# sparkfun-nrf52832-breakout.net
KiCad netlist of a schematic drawn in EAGLE
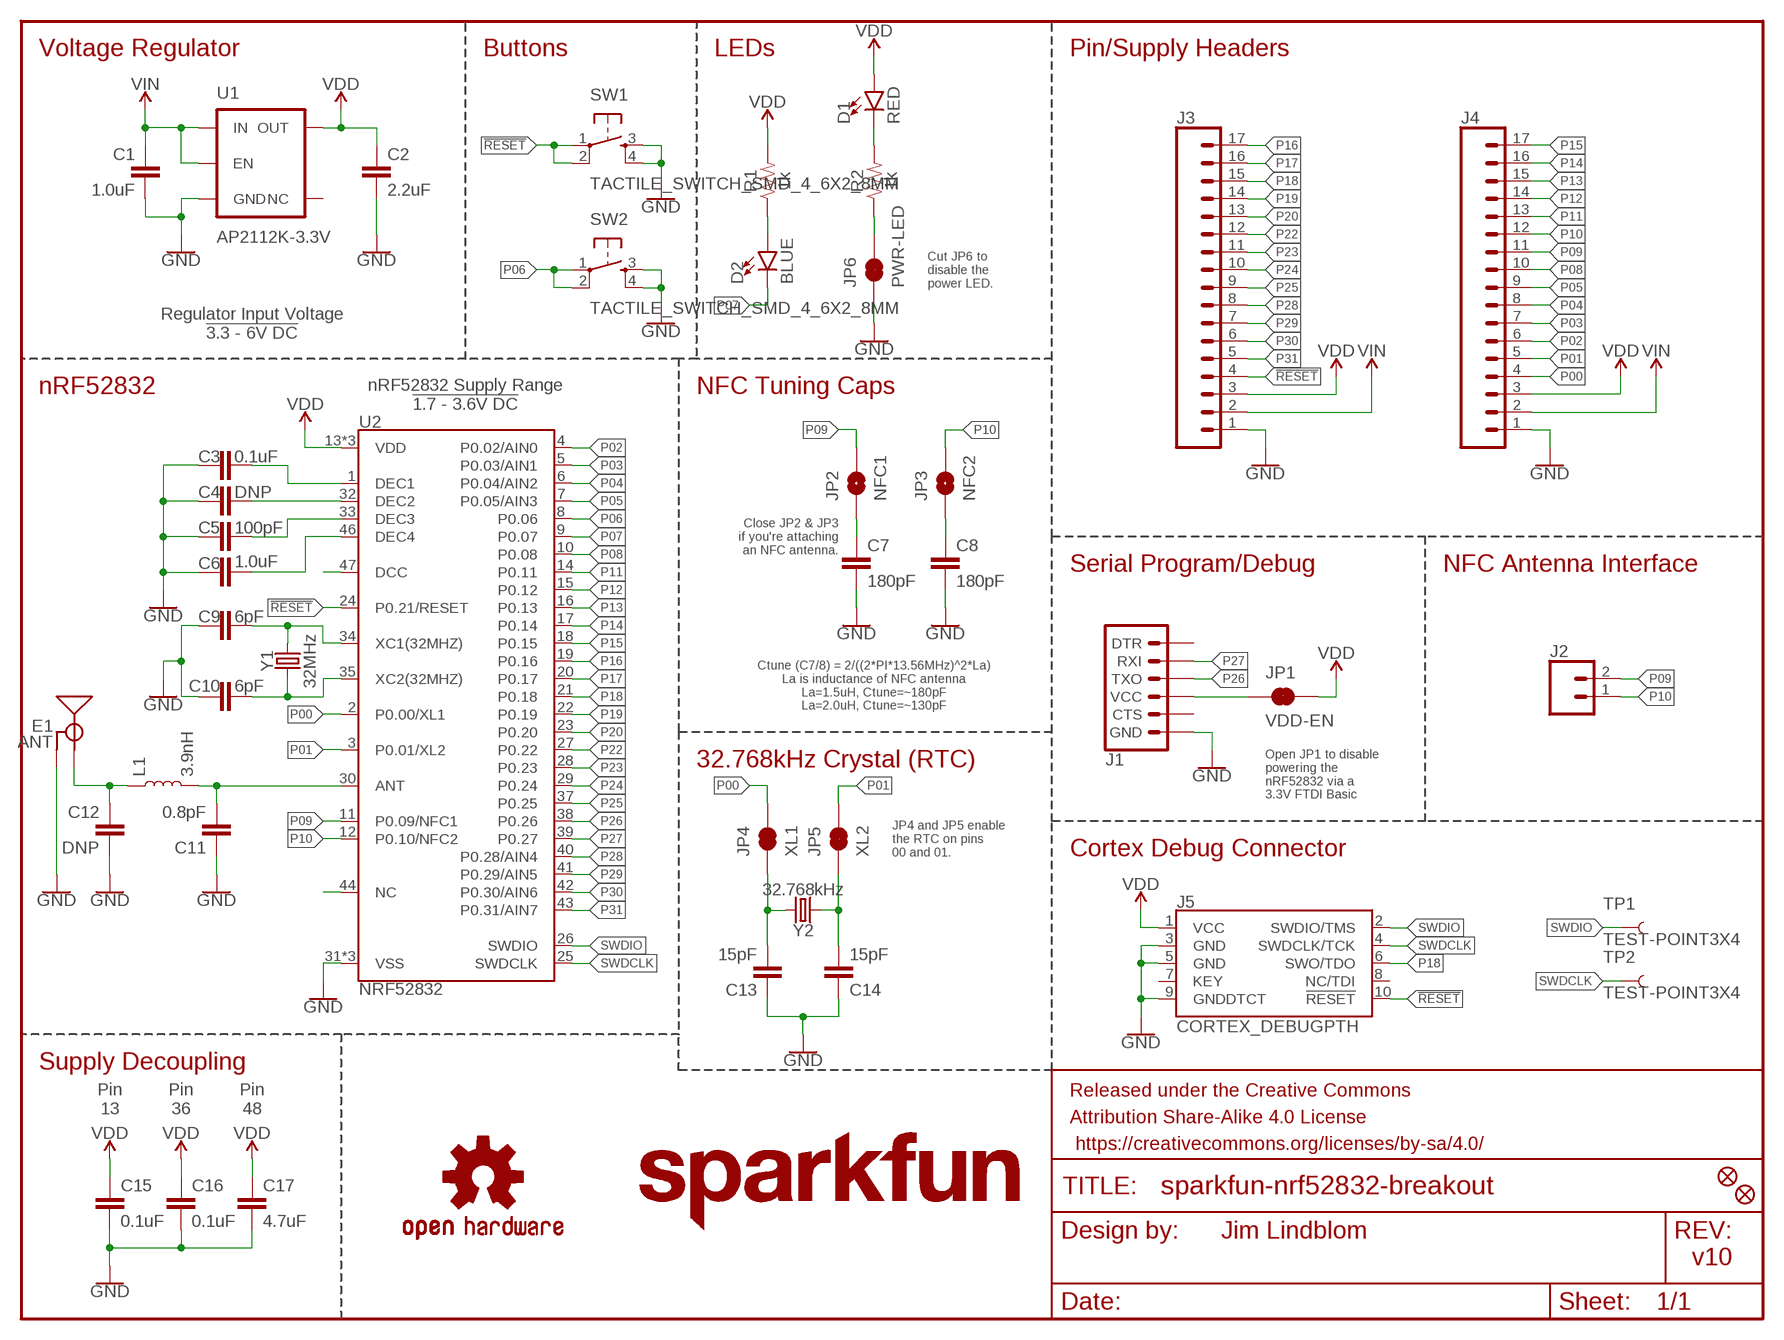
[diagram p0: schematic, sheet 1]

(export (version "E")
  (design (tool "Eeschema 10.0.6"))
  (components
    (comp (ref "C1")
      (value "1.0uF")
      (footprint "eagle-import:0603")
      (libsource (lib "eagle-import") (part "1.0UF-0603-16V-10%"))
    )
    (comp (ref "C2")
      (value "2.2uF")
      (footprint "eagle-import:0603")
      (libsource (lib "eagle-import") (part "2.2UF-0603-10V-20%"))
    )
    (comp (ref "C3")
      (value "0.1uF")
      (footprint "eagle-import:0402")
      (libsource (lib "eagle-import") (part "0.1UF-0402-16V-10%"))
    )
    (comp (ref "C4")
      (value "DNP")
      (footprint "eagle-import:0402")
      (libsource (lib "eagle-import") (part "CAP0402"))
    )
    (comp (ref "C5")
      (value "100pF")
      (footprint "eagle-import:0402")
      (libsource (lib "eagle-import") (part "100PF-0402-50V-5%"))
    )
    (comp (ref "C6")
      (value "1.0uF")
      (footprint "eagle-import:0402")
      (libsource (lib "eagle-import") (part "1.0UF-0402-16V-10%"))
    )
    (comp (ref "C7")
      (value "180pF")
      (footprint "eagle-import:0603")
      (libsource (lib "eagle-import") (part "180PF-0603-50V-5%"))
    )
    (comp (ref "C8")
      (value "180pF")
      (footprint "eagle-import:0603")
      (libsource (lib "eagle-import") (part "180PF-0603-50V-5%"))
    )
    (comp (ref "C9")
      (value "6pF")
      (footprint "eagle-import:0402")
      (libsource (lib "eagle-import") (part "6PF-0402-50V-0.5%"))
    )
    (comp (ref "C10")
      (value "6pF")
      (footprint "eagle-import:0402")
      (libsource (lib "eagle-import") (part "6PF-0402-50V-0.5%"))
    )
    (comp (ref "C11")
      (value "0.8pF")
      (footprint "eagle-import:0402")
      (libsource (lib "eagle-import") (part "0.8PF-0402-50V-0.1PF"))
    )
    (comp (ref "C12")
      (value "DNP")
      (footprint "eagle-import:0402")
      (libsource (lib "eagle-import") (part "CAP0402"))
    )
    (comp (ref "C13")
      (value "15pF")
      (footprint "eagle-import:0402")
      (libsource (lib "eagle-import") (part "15PF-0402-50V-5%"))
    )
    (comp (ref "C14")
      (value "15pF")
      (footprint "eagle-import:0402")
      (libsource (lib "eagle-import") (part "15PF-0402-50V-5%"))
    )
    (comp (ref "C15")
      (value "0.1uF")
      (footprint "eagle-import:0402")
      (libsource (lib "eagle-import") (part "0.1UF-0402-16V-10%"))
    )
    (comp (ref "C16")
      (value "0.1uF")
      (footprint "eagle-import:0402")
      (libsource (lib "eagle-import") (part "0.1UF-0402-16V-10%"))
    )
    (comp (ref "C17")
      (value "4.7uF")
      (footprint "eagle-import:0603")
      (libsource (lib "eagle-import") (part "4.7UF0603"))
    )
    (comp (ref "D1")
      (value "RED")
      (footprint "eagle-import:LED-0603")
      (libsource (lib "eagle-import") (part "LED-RED0603"))
    )
    (comp (ref "D2")
      (value "BLUE")
      (footprint "eagle-import:LED-0603")
      (libsource (lib "eagle-import") (part "LED-BLUE0603"))
    )
    (comp (ref "E1")
      (value "ANT")
      (footprint "eagle-import:TRACE_ANTENNA_2.4GHZ_15.2MM")
      (libsource (lib "eagle-import") (part "ANTENNA-GROUNDEDTRACE-15.2MM"))
    )
    (comp (ref "FD1")
      (value "FIDUCIALUFIDUCIAL")
      (footprint "eagle-import:FIDUCIAL-MICRO")
      (libsource (lib "eagle-import") (part "FIDUCIALUFIDUCIAL"))
    )
    (comp (ref "FD2")
      (value "FIDUCIALUFIDUCIAL")
      (footprint "eagle-import:FIDUCIAL-MICRO")
      (libsource (lib "eagle-import") (part "FIDUCIALUFIDUCIAL"))
    )
    (comp (ref "FRAME1")
      (value "FRAME-LETTER")
      (footprint "eagle-import:CREATIVE_COMMONS")
      (libsource (lib "eagle-import") (part "FRAME-LETTER"))
    )
    (comp (ref "J1")
      (value "ARDUINO_SERIAL_PROGRAMPTH")
      (footprint "eagle-import:1X06")
      (libsource (lib "eagle-import") (part "ARDUINO_SERIAL_PROGRAMPTH"))
    )
    (comp (ref "J2")
      (value "CONN_02PTH")
      (footprint "eagle-import:1X02")
      (libsource (lib "eagle-import") (part "CONN_02PTH"))
    )
    (comp (ref "J3")
      (value "CONN_17")
      (footprint "eagle-import:1X17")
      (libsource (lib "eagle-import") (part "CONN_17"))
    )
    (comp (ref "J4")
      (value "CONN_17")
      (footprint "eagle-import:1X17")
      (libsource (lib "eagle-import") (part "CONN_17"))
    )
    (comp (ref "J5")
      (value "CORTEX_DEBUGPTH")
      (footprint "eagle-import:2X5-PTH-1.27MM")
      (libsource (lib "eagle-import") (part "CORTEX_DEBUGPTH"))
    )
    (comp (ref "JP1")
      (value "VDD-EN")
      (footprint "eagle-import:SMT-JUMPER_2_NC_TRACE_SILK")
      (libsource (lib "eagle-import") (part "JUMPER-SMT_2_NC_TRACE_SILK"))
    )
    (comp (ref "JP2")
      (value "NFC1")
      (footprint "eagle-import:SMT-JUMPER_2_NO_SILK")
      (libsource (lib "eagle-import") (part "JUMPER-SMT_2_NO_SILK"))
    )
    (comp (ref "JP3")
      (value "NFC2")
      (footprint "eagle-import:SMT-JUMPER_2_NO_SILK")
      (libsource (lib "eagle-import") (part "JUMPER-SMT_2_NO_SILK"))
    )
    (comp (ref "JP4")
      (value "XL1")
      (footprint "eagle-import:PAD-JUMPER-2-NC_BY_TRACE_YES_SILK")
      (libsource (lib "eagle-import") (part "JUMPER-PAD-2-NC_BY_TRACE"))
    )
    (comp (ref "JP5")
      (value "XL2")
      (footprint "eagle-import:PAD-JUMPER-2-NC_BY_TRACE_YES_SILK")
      (libsource (lib "eagle-import") (part "JUMPER-PAD-2-NC_BY_TRACE"))
    )
    (comp (ref "JP6")
      (value "PWR-LED")
      (footprint "eagle-import:PAD-JUMPER-2-NC_BY_TRACE_YES_SILK")
      (libsource (lib "eagle-import") (part "JUMPER-PAD-2-NC_BY_TRACE"))
    )
    (comp (ref "L1")
      (value "3.9nH")
      (footprint "eagle-import:0402")
      (libsource (lib "eagle-import") (part "INDUCTOR-0402-3.9NH"))
    )
    (comp (ref "LOGO1")
      (value "OSHW-LOGOMINI")
      (footprint "eagle-import:OSHW-LOGO-MINI")
      (libsource (lib "eagle-import") (part "OSHW-LOGOMINI"))
    )
    (comp (ref "LOGO2")
      (value "SFE_LOGO_NAME.1_INCH")
      (footprint "eagle-import:SFE_LOGO_NAME_.1")
      (libsource (lib "eagle-import") (part "SFE_LOGO_NAME.1_INCH"))
    )
    (comp (ref "LOGO3")
      (value "SFE_LOGO_NAME.1_INCH")
      (footprint "eagle-import:SFE_LOGO_NAME_.1")
      (libsource (lib "eagle-import") (part "SFE_LOGO_NAME.1_INCH"))
    )
    (comp (ref "R1")
      (value "1k")
      (footprint "eagle-import:0603")
      (libsource (lib "eagle-import") (part "1KOHM-0603-1/10W-1%"))
    )
    (comp (ref "R2")
      (value "1k")
      (footprint "eagle-import:0603")
      (libsource (lib "eagle-import") (part "1KOHM-0603-1/10W-1%"))
    )
    (comp (ref "SW1")
      (value "TACTILE_SWITCH_SMD_4_6X2_8MM")
      (footprint "eagle-import:TACTILE_SWITCH_SMD_4.6X2.8MM")
      (libsource (lib "eagle-import") (part "SWITCH_SPST_4_PINRECT"))
    )
    (comp (ref "SW2")
      (value "TACTILE_SWITCH_SMD_4_6X2_8MM")
      (footprint "eagle-import:TACTILE_SWITCH_SMD_4.6X2.8MM")
      (libsource (lib "eagle-import") (part "SWITCH_SPST_4_PINRECT"))
    )
    (comp (ref "TP1")
      (value "TEST-POINT3X4")
      (footprint "eagle-import:PAD.03X.04")
      (libsource (lib "eagle-import") (part "TEST-POINT3X4"))
    )
    (comp (ref "TP2")
      (value "TEST-POINT3X4")
      (footprint "eagle-import:PAD.03X.04")
      (libsource (lib "eagle-import") (part "TEST-POINT3X4"))
    )
    (comp (ref "U1")
      (value "AP2112K-3.3V")
      (footprint "eagle-import:SOT23-5")
      (libsource (lib "eagle-import") (part "V_REG_AP2112K-3.3V"))
    )
    (comp (ref "U2")
      (value "NRF52832")
      (footprint "eagle-import:QFN48-6X6MM")
      (libsource (lib "eagle-import") (part "NRF52832"))
    )
    (comp (ref "Y1")
      (value "32MHz")
      (footprint "eagle-import:CRYSTAL-SMD-2.0X1.6MM")
      (libsource (lib "eagle-import") (part "CRYSTAL-32MHZ-SMD-2.0X1.6MM"))
    )
    (comp (ref "Y2")
      (value "32.768kHz")
      (footprint "eagle-import:CRYSTAL-SMD-3.2X1.5MM")
      (libsource (lib "eagle-import") (part "CRYSTAL-32.768KHZSMD-3.2X1.5"))
    )
  )
  (nets
    (net (code "1") (name "/~{RESET}") (class "Default")
      (node (ref "J3") (pin "4") (pinfunction "4_4") (pintype "passive"))
      (node (ref "J5") (pin "10") (pinfunction "~{RESET}_10") (pintype "bidirectional"))
      (node (ref "SW1") (pin "1") (pinfunction "1_1") (pintype "passive"))
      (node (ref "SW1") (pin "2") (pinfunction "2_2") (pintype "passive"))
      (node (ref "U2") (pin "24") (pinfunction "P0.21/RESET_24") (pintype "bidirectional"))
    )
    (net (code "2") (name "GND") (class "Default")
      (node (ref "C1") (pin "2") (pinfunction "2_2") (pintype "passive"))
      (node (ref "C10") (pin "2") (pinfunction "2_2") (pintype "passive"))
      (node (ref "C11") (pin "1") (pinfunction "1_1") (pintype "passive"))
      (node (ref "C12") (pin "2") (pinfunction "2_2") (pintype "passive"))
      (node (ref "C13") (pin "1") (pinfunction "1_1") (pintype "passive"))
      (node (ref "C14") (pin "1") (pinfunction "1_1") (pintype "passive"))
      (node (ref "C15") (pin "2") (pinfunction "2_2") (pintype "passive"))
      (node (ref "C16") (pin "2") (pinfunction "2_2") (pintype "passive"))
      (node (ref "C17") (pin "2") (pinfunction "2_2") (pintype "passive"))
      (node (ref "C2") (pin "2") (pinfunction "2_2") (pintype "passive"))
      (node (ref "C3") (pin "1") (pinfunction "1_1") (pintype "passive"))
      (node (ref "C4") (pin "1") (pinfunction "1_1") (pintype "passive"))
      (node (ref "C5") (pin "1") (pinfunction "1_1") (pintype "passive"))
      (node (ref "C6") (pin "1") (pinfunction "1_1") (pintype "passive"))
      (node (ref "C7") (pin "2") (pinfunction "2_2") (pintype "passive"))
      (node (ref "C8") (pin "2") (pinfunction "2_2") (pintype "passive"))
      (node (ref "C9") (pin "1") (pinfunction "1_1") (pintype "passive"))
      (node (ref "E1") (pin "GND") (pinfunction "GND_GND") (pintype "bidirectional"))
      (node (ref "J1") (pin "6") (pinfunction "GND_6") (pintype "passive"))
      (node (ref "J3") (pin "1") (pinfunction "1_1") (pintype "passive"))
      (node (ref "J4") (pin "1") (pinfunction "1_1") (pintype "passive"))
      (node (ref "J5") (pin "3") (pinfunction "GND_3") (pintype "bidirectional"))
      (node (ref "J5") (pin "5") (pinfunction "GND_5") (pintype "bidirectional"))
      (node (ref "J5") (pin "9") (pinfunction "GNDDTCT_9") (pintype "bidirectional"))
      (node (ref "JP6") (pin "1") (pinfunction "1_1") (pintype "passive"))
      (node (ref "SW1") (pin "3") (pinfunction "3_3") (pintype "passive"))
      (node (ref "SW1") (pin "4") (pinfunction "4_4") (pintype "passive"))
      (node (ref "SW2") (pin "3") (pinfunction "3_3") (pintype "passive"))
      (node (ref "SW2") (pin "4") (pinfunction "4_4") (pintype "passive"))
      (node (ref "U1") (pin "2") (pinfunction "GND_2") (pintype "input"))
      (node (ref "U2") (pin "31") (pinfunction "VSS_31") (pintype "bidirectional"))
      (node (ref "U2") (pin "45") (pinfunction "VSS_45") (pintype "bidirectional"))
      (node (ref "U2") (pin "EP") (pinfunction "VSS_EP") (pintype "bidirectional"))
    )
    (net (code "3") (name "Net-(C7-Pad1)") (class "Default")
      (node (ref "C7") (pin "1") (pinfunction "1_1") (pintype "passive"))
      (node (ref "JP2") (pin "1") (pinfunction "1_1") (pintype "passive"))
    )
    (net (code "4") (name "Net-(C8-Pad1)") (class "Default")
      (node (ref "C8") (pin "1") (pinfunction "1_1") (pintype "passive"))
      (node (ref "JP3") (pin "1") (pinfunction "1_1") (pintype "passive"))
    )
    (net (code "5") (name "Net-(D1-PadC)") (class "Default")
      (node (ref "D1") (pin "C") (pinfunction "C_C") (pintype "passive"))
      (node (ref "R2") (pin "2") (pinfunction "2_2") (pintype "passive"))
    )
    (net (code "6") (name "Net-(D2-PadA)") (class "Default")
      (node (ref "D2") (pin "A") (pinfunction "A_A") (pintype "passive"))
      (node (ref "R1") (pin "1") (pinfunction "1_1") (pintype "passive"))
    )
    (net (code "7") (name "Net-(E1-SIGNAL)") (class "Default")
      (node (ref "C12") (pin "1") (pinfunction "1_1") (pintype "passive"))
      (node (ref "E1") (pin "ANT") (pinfunction "SIGNAL_ANT") (pintype "bidirectional"))
      (node (ref "L1") (pin "1") (pinfunction "1_1") (pintype "passive"))
    )
    (net (code "8") (name "Net-(J1-VCC)") (class "Default")
      (node (ref "J1") (pin "4") (pinfunction "VCC_4") (pintype "passive"))
      (node (ref "JP1") (pin "1") (pinfunction "1_1") (pintype "passive"))
    )
    (net (code "9") (name "Net-(JP6-Pad2)") (class "Default")
      (node (ref "JP6") (pin "2") (pinfunction "2_2") (pintype "passive"))
      (node (ref "R2") (pin "1") (pinfunction "1_1") (pintype "passive"))
    )
    (net (code "10") (name "Net-(U2-ANT)") (class "Default")
      (node (ref "C11") (pin "2") (pinfunction "2_2") (pintype "passive"))
      (node (ref "L1") (pin "2") (pinfunction "2_2") (pintype "passive"))
      (node (ref "U2") (pin "30") (pinfunction "ANT_30") (pintype "bidirectional"))
    )
    (net (code "11") (name "Net-(U2-DEC1)") (class "Default")
      (node (ref "C3") (pin "2") (pinfunction "2_2") (pintype "passive"))
      (node (ref "U2") (pin "1") (pinfunction "DEC1_1") (pintype "bidirectional"))
    )
    (net (code "12") (name "Net-(U2-DEC2)") (class "Default")
      (node (ref "C4") (pin "2") (pinfunction "2_2") (pintype "passive"))
      (node (ref "U2") (pin "32") (pinfunction "DEC2_32") (pintype "bidirectional"))
    )
    (net (code "13") (name "Net-(U2-DEC3)") (class "Default")
      (node (ref "C5") (pin "2") (pinfunction "2_2") (pintype "passive"))
      (node (ref "U2") (pin "33") (pinfunction "DEC3_33") (pintype "bidirectional"))
    )
    (net (code "14") (name "Net-(U2-DEC4)") (class "Default")
      (node (ref "C6") (pin "2") (pinfunction "2_2") (pintype "passive"))
      (node (ref "U2") (pin "46") (pinfunction "DEC4_46") (pintype "bidirectional"))
    )
    (net (code "15") (name "Net-(U2-XC1(32MHZ))") (class "Default")
      (node (ref "C9") (pin "2") (pinfunction "2_2") (pintype "passive"))
      (node (ref "U2") (pin "34") (pinfunction "XC1(32MHZ)_34") (pintype "bidirectional"))
      (node (ref "Y1") (pin "3") (pinfunction "2_3") (pintype "passive"))
    )
    (net (code "16") (name "Net-(U2-XC2(32MHZ))") (class "Default")
      (node (ref "C10") (pin "1") (pinfunction "1_1") (pintype "passive"))
      (node (ref "U2") (pin "35") (pinfunction "XC2(32MHZ)_35") (pintype "bidirectional"))
      (node (ref "Y1") (pin "1") (pinfunction "1_1") (pintype "passive"))
    )
    (net (code "17") (name "Net-(Y2-1)") (class "Default")
      (node (ref "C14") (pin "2") (pinfunction "2_2") (pintype "passive"))
      (node (ref "JP5") (pin "1") (pinfunction "1_1") (pintype "passive"))
      (node (ref "Y2") (pin "P$1") (pinfunction "1_P$1") (pintype "passive"))
    )
    (net (code "18") (name "Net-(Y2-2)") (class "Default")
      (node (ref "C13") (pin "2") (pinfunction "2_2") (pintype "passive"))
      (node (ref "JP4") (pin "1") (pinfunction "1_1") (pintype "passive"))
      (node (ref "Y2") (pin "P$2") (pinfunction "2_P$2") (pintype "passive"))
    )
    (net (code "19") (name "P00") (class "Default")
      (node (ref "J4") (pin "4") (pinfunction "4_4") (pintype "passive"))
      (node (ref "JP4") (pin "2") (pinfunction "2_2") (pintype "passive"))
      (node (ref "U2") (pin "2") (pinfunction "P0.00/XL1_2") (pintype "bidirectional"))
    )
    (net (code "20") (name "P01") (class "Default")
      (node (ref "J4") (pin "5") (pinfunction "5_5") (pintype "passive"))
      (node (ref "JP5") (pin "2") (pinfunction "2_2") (pintype "passive"))
      (node (ref "U2") (pin "3") (pinfunction "P0.01/XL2_3") (pintype "bidirectional"))
    )
    (net (code "21") (name "P02") (class "Default")
      (node (ref "J4") (pin "6") (pinfunction "6_6") (pintype "passive"))
      (node (ref "U2") (pin "4") (pinfunction "P0.02/AIN0_4") (pintype "bidirectional"))
    )
    (net (code "22") (name "P03") (class "Default")
      (node (ref "J4") (pin "7") (pinfunction "7_7") (pintype "passive"))
      (node (ref "U2") (pin "5") (pinfunction "P0.03/AIN1_5") (pintype "bidirectional"))
    )
    (net (code "23") (name "P04") (class "Default")
      (node (ref "J4") (pin "8") (pinfunction "8_8") (pintype "passive"))
      (node (ref "U2") (pin "6") (pinfunction "P0.04/AIN2_6") (pintype "bidirectional"))
    )
    (net (code "24") (name "P05") (class "Default")
      (node (ref "J4") (pin "9") (pinfunction "9_9") (pintype "passive"))
      (node (ref "U2") (pin "7") (pinfunction "P0.05/AIN3_7") (pintype "bidirectional"))
    )
    (net (code "25") (name "P06") (class "Default")
      (node (ref "SW2") (pin "1") (pinfunction "1_1") (pintype "passive"))
      (node (ref "SW2") (pin "2") (pinfunction "2_2") (pintype "passive"))
      (node (ref "U2") (pin "8") (pinfunction "P0.06_8") (pintype "bidirectional"))
    )
    (net (code "26") (name "P07") (class "Default")
      (node (ref "D2") (pin "C") (pinfunction "C_C") (pintype "passive"))
      (node (ref "U2") (pin "9") (pinfunction "P0.07_9") (pintype "bidirectional"))
    )
    (net (code "27") (name "P08") (class "Default")
      (node (ref "J4") (pin "10") (pinfunction "10_10") (pintype "passive"))
      (node (ref "U2") (pin "10") (pinfunction "P0.08_10") (pintype "bidirectional"))
    )
    (net (code "28") (name "P09") (class "Default")
      (node (ref "J2") (pin "2") (pinfunction "2_2") (pintype "passive"))
      (node (ref "J4") (pin "11") (pinfunction "11_11") (pintype "passive"))
      (node (ref "JP2") (pin "2") (pinfunction "2_2") (pintype "passive"))
      (node (ref "U2") (pin "11") (pinfunction "P0.09/NFC1_11") (pintype "bidirectional"))
    )
    (net (code "29") (name "P10") (class "Default")
      (node (ref "J2") (pin "1") (pinfunction "1_1") (pintype "passive"))
      (node (ref "J4") (pin "12") (pinfunction "12_12") (pintype "passive"))
      (node (ref "JP3") (pin "2") (pinfunction "2_2") (pintype "passive"))
      (node (ref "U2") (pin "12") (pinfunction "P0.10/NFC2_12") (pintype "bidirectional"))
    )
    (net (code "30") (name "P11") (class "Default")
      (node (ref "J4") (pin "13") (pinfunction "13_13") (pintype "passive"))
      (node (ref "U2") (pin "14") (pinfunction "P0.11_14") (pintype "bidirectional"))
    )
    (net (code "31") (name "P12") (class "Default")
      (node (ref "J4") (pin "14") (pinfunction "14_14") (pintype "passive"))
      (node (ref "U2") (pin "15") (pinfunction "P0.12_15") (pintype "bidirectional"))
    )
    (net (code "32") (name "P13") (class "Default")
      (node (ref "J4") (pin "15") (pinfunction "15_15") (pintype "passive"))
      (node (ref "U2") (pin "16") (pinfunction "P0.13_16") (pintype "bidirectional"))
    )
    (net (code "33") (name "P14") (class "Default")
      (node (ref "J4") (pin "16") (pinfunction "16_16") (pintype "passive"))
      (node (ref "U2") (pin "17") (pinfunction "P0.14_17") (pintype "bidirectional"))
    )
    (net (code "34") (name "P15") (class "Default")
      (node (ref "J4") (pin "17") (pinfunction "17_17") (pintype "passive"))
      (node (ref "U2") (pin "18") (pinfunction "P0.15_18") (pintype "bidirectional"))
    )
    (net (code "35") (name "P16") (class "Default")
      (node (ref "J3") (pin "17") (pinfunction "17_17") (pintype "passive"))
      (node (ref "U2") (pin "19") (pinfunction "P0.16_19") (pintype "bidirectional"))
    )
    (net (code "36") (name "P17") (class "Default")
      (node (ref "J3") (pin "16") (pinfunction "16_16") (pintype "passive"))
      (node (ref "U2") (pin "20") (pinfunction "P0.17_20") (pintype "bidirectional"))
    )
    (net (code "37") (name "P18") (class "Default")
      (node (ref "J3") (pin "15") (pinfunction "15_15") (pintype "passive"))
      (node (ref "J5") (pin "6") (pinfunction "SWO/TDO_6") (pintype "bidirectional"))
      (node (ref "U2") (pin "21") (pinfunction "P0.18_21") (pintype "bidirectional"))
    )
    (net (code "38") (name "P19") (class "Default")
      (node (ref "J3") (pin "14") (pinfunction "14_14") (pintype "passive"))
      (node (ref "U2") (pin "22") (pinfunction "P0.19_22") (pintype "bidirectional"))
    )
    (net (code "39") (name "P20") (class "Default")
      (node (ref "J3") (pin "13") (pinfunction "13_13") (pintype "passive"))
      (node (ref "U2") (pin "23") (pinfunction "P0.20_23") (pintype "bidirectional"))
    )
    (net (code "40") (name "P22") (class "Default")
      (node (ref "J3") (pin "12") (pinfunction "12_12") (pintype "passive"))
      (node (ref "U2") (pin "27") (pinfunction "P0.22_27") (pintype "bidirectional"))
    )
    (net (code "41") (name "P23") (class "Default")
      (node (ref "J3") (pin "11") (pinfunction "11_11") (pintype "passive"))
      (node (ref "U2") (pin "28") (pinfunction "P0.23_28") (pintype "bidirectional"))
    )
    (net (code "42") (name "P24") (class "Default")
      (node (ref "J3") (pin "10") (pinfunction "10_10") (pintype "passive"))
      (node (ref "U2") (pin "29") (pinfunction "P0.24_29") (pintype "bidirectional"))
    )
    (net (code "43") (name "P25") (class "Default")
      (node (ref "J3") (pin "9") (pinfunction "9_9") (pintype "passive"))
      (node (ref "U2") (pin "37") (pinfunction "P0.25_37") (pintype "bidirectional"))
    )
    (net (code "44") (name "P26") (class "Default")
      (node (ref "J1") (pin "3") (pinfunction "TXO_3") (pintype "passive"))
      (node (ref "U2") (pin "38") (pinfunction "P0.26_38") (pintype "bidirectional"))
    )
    (net (code "45") (name "P27") (class "Default")
      (node (ref "J1") (pin "2") (pinfunction "RXI_2") (pintype "passive"))
      (node (ref "U2") (pin "39") (pinfunction "P0.27_39") (pintype "bidirectional"))
    )
    (net (code "46") (name "P28") (class "Default")
      (node (ref "J3") (pin "8") (pinfunction "8_8") (pintype "passive"))
      (node (ref "U2") (pin "40") (pinfunction "P0.28/AIN4_40") (pintype "bidirectional"))
    )
    (net (code "47") (name "P29") (class "Default")
      (node (ref "J3") (pin "7") (pinfunction "7_7") (pintype "passive"))
      (node (ref "U2") (pin "41") (pinfunction "P0.29/AIN5_41") (pintype "bidirectional"))
    )
    (net (code "48") (name "P30") (class "Default")
      (node (ref "J3") (pin "6") (pinfunction "6_6") (pintype "passive"))
      (node (ref "U2") (pin "42") (pinfunction "P0.30/AIN6_42") (pintype "bidirectional"))
    )
    (net (code "49") (name "P31") (class "Default")
      (node (ref "J3") (pin "5") (pinfunction "5_5") (pintype "passive"))
      (node (ref "U2") (pin "43") (pinfunction "P0.31/AIN7_43") (pintype "bidirectional"))
    )
    (net (code "50") (name "SWDCLK") (class "Default")
      (node (ref "J5") (pin "4") (pinfunction "SWDCLK/TCK_4") (pintype "bidirectional"))
      (node (ref "TP2") (pin "P$1") (pinfunction "1_P$1") (pintype "bidirectional"))
      (node (ref "U2") (pin "25") (pinfunction "SWDCLK_25") (pintype "bidirectional"))
    )
    (net (code "51") (name "SWDIO") (class "Default")
      (node (ref "J5") (pin "2") (pinfunction "SWDIO/TMS_2") (pintype "bidirectional"))
      (node (ref "TP1") (pin "P$1") (pinfunction "1_P$1") (pintype "bidirectional"))
      (node (ref "U2") (pin "26") (pinfunction "SWDIO_26") (pintype "bidirectional"))
    )
    (net (code "52") (name "VDD") (class "Default")
      (node (ref "C15") (pin "1") (pinfunction "1_1") (pintype "passive"))
      (node (ref "C16") (pin "1") (pinfunction "1_1") (pintype "passive"))
      (node (ref "C17") (pin "1") (pinfunction "1_1") (pintype "passive"))
      (node (ref "C2") (pin "1") (pinfunction "1_1") (pintype "passive"))
      (node (ref "D1") (pin "A") (pinfunction "A_A") (pintype "passive"))
      (node (ref "J3") (pin "3") (pinfunction "3_3") (pintype "passive"))
      (node (ref "J4") (pin "3") (pinfunction "3_3") (pintype "passive"))
      (node (ref "J5") (pin "1") (pinfunction "VCC_1") (pintype "bidirectional"))
      (node (ref "JP1") (pin "2") (pinfunction "2_2") (pintype "passive"))
      (node (ref "R1") (pin "2") (pinfunction "2_2") (pintype "passive"))
      (node (ref "U1") (pin "5") (pinfunction "OUT_5") (pintype "passive"))
      (node (ref "U2") (pin "13") (pinfunction "VDD_13") (pintype "bidirectional"))
      (node (ref "U2") (pin "36") (pinfunction "VDD_36") (pintype "bidirectional"))
      (node (ref "U2") (pin "48") (pinfunction "VDD_48") (pintype "bidirectional"))
    )
    (net (code "53") (name "VIN") (class "Default")
      (node (ref "C1") (pin "1") (pinfunction "1_1") (pintype "passive"))
      (node (ref "J3") (pin "2") (pinfunction "2_2") (pintype "passive"))
      (node (ref "J4") (pin "2") (pinfunction "2_2") (pintype "passive"))
      (node (ref "U1") (pin "1") (pinfunction "IN_1") (pintype "input"))
      (node (ref "U1") (pin "3") (pinfunction "EN_3") (pintype "input"))
    )
    (net (code "54") (name "unconnected-(J1-CTS-Pad5)") (class "Default")
      (node (ref "J1") (pin "5") (pinfunction "CTS_5") (pintype "passive"))
    )
    (net (code "55") (name "unconnected-(J1-DTR-Pad1)") (class "Default")
      (node (ref "J1") (pin "1") (pinfunction "DTR_1") (pintype "passive"))
    )
    (net (code "56") (name "unconnected-(J5-KEY-Pad7)") (class "Default")
      (node (ref "J5") (pin "7") (pinfunction "KEY_7") (pintype "bidirectional"))
    )
    (net (code "57") (name "unconnected-(J5-NC{slash}TDI-Pad8)") (class "Default")
      (node (ref "J5") (pin "8") (pinfunction "NC/TDI_8") (pintype "bidirectional"))
    )
    (net (code "58") (name "unconnected-(U1-NC-Pad4)") (class "Default")
      (node (ref "U1") (pin "4") (pinfunction "NC_4") (pintype "input"))
    )
    (net (code "59") (name "unconnected-(U2-DCC-Pad47)") (class "Default")
      (node (ref "U2") (pin "47") (pinfunction "DCC_47") (pintype "bidirectional"))
    )
    (net (code "60") (name "unconnected-(U2-NC-Pad44)") (class "Default")
      (node (ref "U2") (pin "44") (pinfunction "NC_44") (pintype "bidirectional"))
    )
  )
)
